# USB.net
KiCad netlist of a schematic drawn in Altium Designer
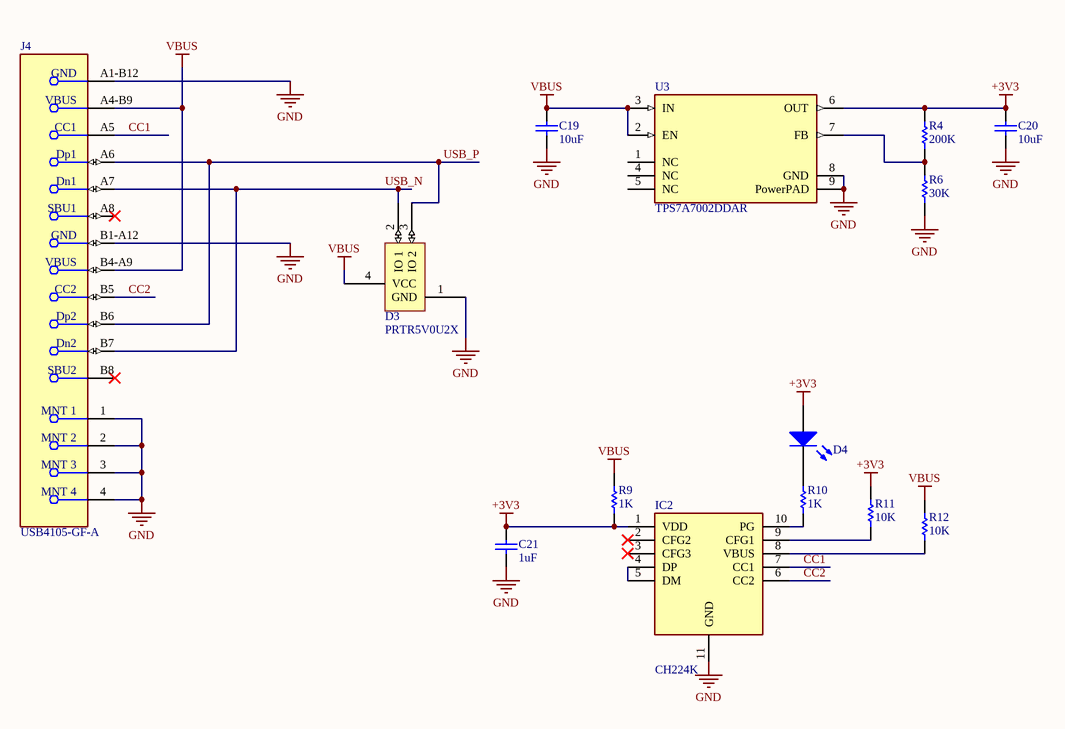
[diagram p0: USB.SchDoc]

(export (version "E")
  (design (tool "Eeschema 10.0.6"))
  (components
    (comp (ref "C19")
      (value "10uF")
      (footprint "C603")
      (description "Capacitor")
      (fields (field (name "DESIGNER") "Parsa Malekpour"))
      (libsource (lib "ParsaLibrary") (part "Cap"))
    )
    (comp (ref "C20")
      (value "10uF")
      (footprint "C603")
      (description "Capacitor")
      (fields (field (name "DESIGNER") "Parsa Malekpour"))
      (libsource (lib "ParsaLibrary") (part "Cap"))
    )
    (comp (ref "C21")
      (value "1uF")
      (footprint "C603")
      (description "Capacitor")
      (fields (field (name "DESIGNER") "Parsa Malekpour"))
      (libsource (lib "ParsaLibrary") (part "Cap"))
    )
    (comp (ref "D3")
      (value "PRTR5V0U2X")
      (footprint "SOT-143B")
      (description "Ultra low capacitance double rail-to-rail ESD protection diode")
      (libsource (lib "ParsaLibrary") (part "PRTR5V0U2X"))
    )
    (comp (ref "D4") (value "LED") (footprint "led-0603") (libsource (lib "ParsaLibrary") (part "LED")))
    (comp (ref "IC2")
      (value "CH224K")
      (footprint "SamacSys:SOP100P600X180-11N")
      (description "Integrated Circuit")
      (libsource (lib "*") (part "CH224K"))
    )
    (comp (ref "J4")
      (value "USB4105-GF-A")
      (footprint "FP-USB4105-GF-A-MFG")
      (description "CONN RCPT USB2.0 TYPEC 5A")
      (fields
        (field (name "MANUFACTURER") "GCT")
        (field (name "OCTOPART") "https://octopart.com/usb4105-gf-a-gct-106627878")
      )
      (libsource (lib "Altium Content Vault") (part "e7c17a616881a82b79941196b4bec10"))
    )
    (comp (ref "R4")
      (value "200K")
      (footprint "R0603")
      (description "Resistor")
      (fields (field (name "DESIGNER") "Parsa Malekpour"))
      (libsource (lib "ParsaLibrary") (part "Resistor"))
    )
    (comp (ref "R6")
      (value "30K")
      (footprint "R0603")
      (description "Resistor")
      (fields (field (name "DESIGNER") "Parsa Malekpour"))
      (libsource (lib "ParsaLibrary") (part "Resistor"))
    )
    (comp (ref "R9")
      (value "1K")
      (footprint "R0603")
      (description "Resistor")
      (fields (field (name "DESIGNER") "Parsa Malekpour"))
      (libsource (lib "ParsaLibrary") (part "Resistor"))
    )
    (comp (ref "R10")
      (value "1K")
      (footprint "R0603")
      (description "Resistor")
      (fields (field (name "DESIGNER") "Parsa Malekpour"))
      (libsource (lib "ParsaLibrary") (part "Resistor"))
    )
    (comp (ref "R11")
      (value "10K")
      (footprint "R0603")
      (description "Resistor")
      (fields (field (name "DESIGNER") "Parsa Malekpour"))
      (libsource (lib "ParsaLibrary") (part "Resistor"))
    )
    (comp (ref "R12")
      (value "10K")
      (footprint "R0603")
      (description "Resistor")
      (fields (field (name "DESIGNER") "Parsa Malekpour"))
      (libsource (lib "ParsaLibrary") (part "Resistor"))
    )
    (comp (ref "U3")
      (value "TPS7A7002DDAR")
      (footprint "FP-DDA0008E-IPC_A")
      (description "IC REG LIN POS ADJ 3A 8SO PWRPAD")
      (libsource (lib "Altium Content Vault") (part "faebeb2d6e46d862d344f00b777028a"))
    )
  )
  (nets
    (net (code "1") (name "+3V3") (class "Default")
      (node (ref "C20") (pin "2") (pinfunction "2_2") (pintype "passive"))
      (node (ref "C21") (pin "2") (pinfunction "2_2") (pintype "passive"))
      (node (ref "D4") (pin "1") (pinfunction "A_1") (pintype "passive"))
      (node (ref "IC2") (pin "1") (pinfunction "VDD_1") (pintype "passive"))
      (node (ref "R11") (pin "2") (pinfunction "2_2") (pintype "passive"))
      (node (ref "R4") (pin "2") (pinfunction "2_2") (pintype "passive"))
      (node (ref "R9") (pin "1") (pinfunction "1_1") (pintype "passive"))
      (node (ref "U3") (pin "6") (pinfunction "OUT_6") (pintype "output"))
    )
    (net (code "2") (name "/CC1") (class "Default")
      (node (ref "IC2") (pin "7") (pinfunction "CC1_7") (pintype "passive"))
      (node (ref "J4") (pin "A5") (pinfunction "CC1_A5") (pintype "power_in"))
    )
    (net (code "3") (name "/CC2") (class "Default")
      (node (ref "IC2") (pin "6") (pinfunction "CC2_6") (pintype "passive"))
      (node (ref "J4") (pin "B5") (pinfunction "CC2_B5") (pintype "bidirectional"))
    )
    (net (code "4") (name "/USB_N") (class "Default")
      (node (ref "D3") (pin "2") (pinfunction "IO_1_2") (pintype "bidirectional"))
      (node (ref "J4") (pin "A7") (pinfunction "Dn1_A7") (pintype "bidirectional"))
      (node (ref "J4") (pin "B7") (pinfunction "Dn2_B7") (pintype "bidirectional"))
    )
    (net (code "5") (name "/USB_P") (class "Default")
      (node (ref "D3") (pin "3") (pinfunction "IO_2_3") (pintype "bidirectional"))
      (node (ref "J4") (pin "A6") (pinfunction "Dp1_A6") (pintype "bidirectional"))
      (node (ref "J4") (pin "B6") (pinfunction "Dp2_B6") (pintype "bidirectional"))
    )
    (net (code "6") (name "GND") (class "Default")
      (node (ref "C19") (pin "1") (pinfunction "1_1") (pintype "passive"))
      (node (ref "C20") (pin "1") (pinfunction "1_1") (pintype "passive"))
      (node (ref "C21") (pin "1") (pinfunction "1_1") (pintype "passive"))
      (node (ref "D3") (pin "1") (pinfunction "GND_1") (pintype "power_in"))
      (node (ref "IC2") (pin "11") (pinfunction "GND_11") (pintype "passive"))
      (node (ref "J4") (pin "1") (pinfunction "MNT_1_1") (pintype "power_in"))
      (node (ref "J4") (pin "2") (pinfunction "MNT_2_2") (pintype "power_in"))
      (node (ref "J4") (pin "3") (pinfunction "MNT_3_3") (pintype "power_in"))
      (node (ref "J4") (pin "4") (pinfunction "MNT_4_4") (pintype "power_in"))
      (node (ref "J4") (pin "A1-B12") (pinfunction "GND_A1-B12") (pintype "power_in"))
      (node (ref "J4") (pin "B1-A12") (pinfunction "GND_B1-A12") (pintype "bidirectional"))
      (node (ref "R6") (pin "1") (pinfunction "1_1") (pintype "passive"))
      (node (ref "U3") (pin "8") (pinfunction "GND_8") (pintype "power_in"))
      (node (ref "U3") (pin "9") (pinfunction "PowerPAD_9") (pintype "power_in"))
    )
    (net (code "7") (name "Net-(D4-K)") (class "Default")
      (node (ref "D4") (pin "2") (pinfunction "K_2") (pintype "passive"))
      (node (ref "R10") (pin "2") (pinfunction "2_2") (pintype "passive"))
    )
    (net (code "8") (name "Net-(IC2-CFG1)") (class "Default")
      (node (ref "IC2") (pin "9") (pinfunction "CFG1_9") (pintype "passive"))
      (node (ref "R11") (pin "1") (pinfunction "1_1") (pintype "passive"))
    )
    (net (code "9") (name "Net-(IC2-DM)") (class "Default")
      (node (ref "IC2") (pin "4") (pinfunction "DP_4") (pintype "passive"))
      (node (ref "IC2") (pin "5") (pinfunction "DM_5") (pintype "passive"))
    )
    (net (code "10") (name "Net-(IC2-PG)") (class "Default")
      (node (ref "IC2") (pin "10") (pinfunction "PG_10") (pintype "passive"))
      (node (ref "R10") (pin "1") (pinfunction "1_1") (pintype "passive"))
    )
    (net (code "11") (name "Net-(IC2-VBUS)") (class "Default")
      (node (ref "IC2") (pin "8") (pinfunction "VBUS_8") (pintype "passive"))
      (node (ref "R12") (pin "1") (pinfunction "1_1") (pintype "passive"))
    )
    (net (code "12") (name "Net-(U3-FB)") (class "Default")
      (node (ref "R4") (pin "1") (pinfunction "1_1") (pintype "passive"))
      (node (ref "R6") (pin "2") (pinfunction "2_2") (pintype "passive"))
      (node (ref "U3") (pin "7") (pinfunction "FB_7") (pintype "output"))
    )
    (net (code "13") (name "VBUS") (class "Default")
      (node (ref "C19") (pin "2") (pinfunction "2_2") (pintype "passive"))
      (node (ref "D3") (pin "4") (pinfunction "VCC_4") (pintype "power_in"))
      (node (ref "J4") (pin "A4-B9") (pinfunction "VBUS_A4-B9") (pintype "power_in"))
      (node (ref "J4") (pin "B4-A9") (pinfunction "VBUS_B4-A9") (pintype "bidirectional"))
      (node (ref "R12") (pin "2") (pinfunction "2_2") (pintype "passive"))
      (node (ref "R9") (pin "2") (pinfunction "2_2") (pintype "passive"))
      (node (ref "U3") (pin "2") (pinfunction "EN_2") (pintype "input"))
      (node (ref "U3") (pin "3") (pinfunction "IN_3") (pintype "input"))
    )
    (net (code "14") (name "unconnected-(IC2-CFG2-Pad2)") (class "Default")
      (node (ref "IC2") (pin "2") (pinfunction "CFG2_2") (pintype "passive+no_connect"))
    )
    (net (code "15") (name "unconnected-(IC2-CFG3-Pad3)") (class "Default")
      (node (ref "IC2") (pin "3") (pinfunction "CFG3_3") (pintype "passive+no_connect"))
    )
    (net (code "16") (name "unconnected-(J4-SBU1-PadA8)") (class "Default")
      (node (ref "J4") (pin "A8") (pinfunction "SBU1_A8") (pintype "bidirectional+no_connect"))
    )
    (net (code "17") (name "unconnected-(J4-SBU2-PadB8)") (class "Default")
      (node (ref "J4") (pin "B8") (pinfunction "SBU2_B8") (pintype "power_in+no_connect"))
    )
    (net (code "18") (name "unconnected-(U3-NC-Pad1)") (class "Default")
      (node (ref "U3") (pin "1") (pinfunction "NC_1") (pintype "passive"))
    )
    (net (code "19") (name "unconnected-(U3-NC-Pad4)") (class "Default")
      (node (ref "U3") (pin "4") (pinfunction "NC_4") (pintype "passive"))
    )
    (net (code "20") (name "unconnected-(U3-NC-Pad5)") (class "Default")
      (node (ref "U3") (pin "5") (pinfunction "NC_5") (pintype "passive"))
    )
  )
)
